# MQTTDoorBell.net
KiCad netlist of a schematic drawn in EAGLE
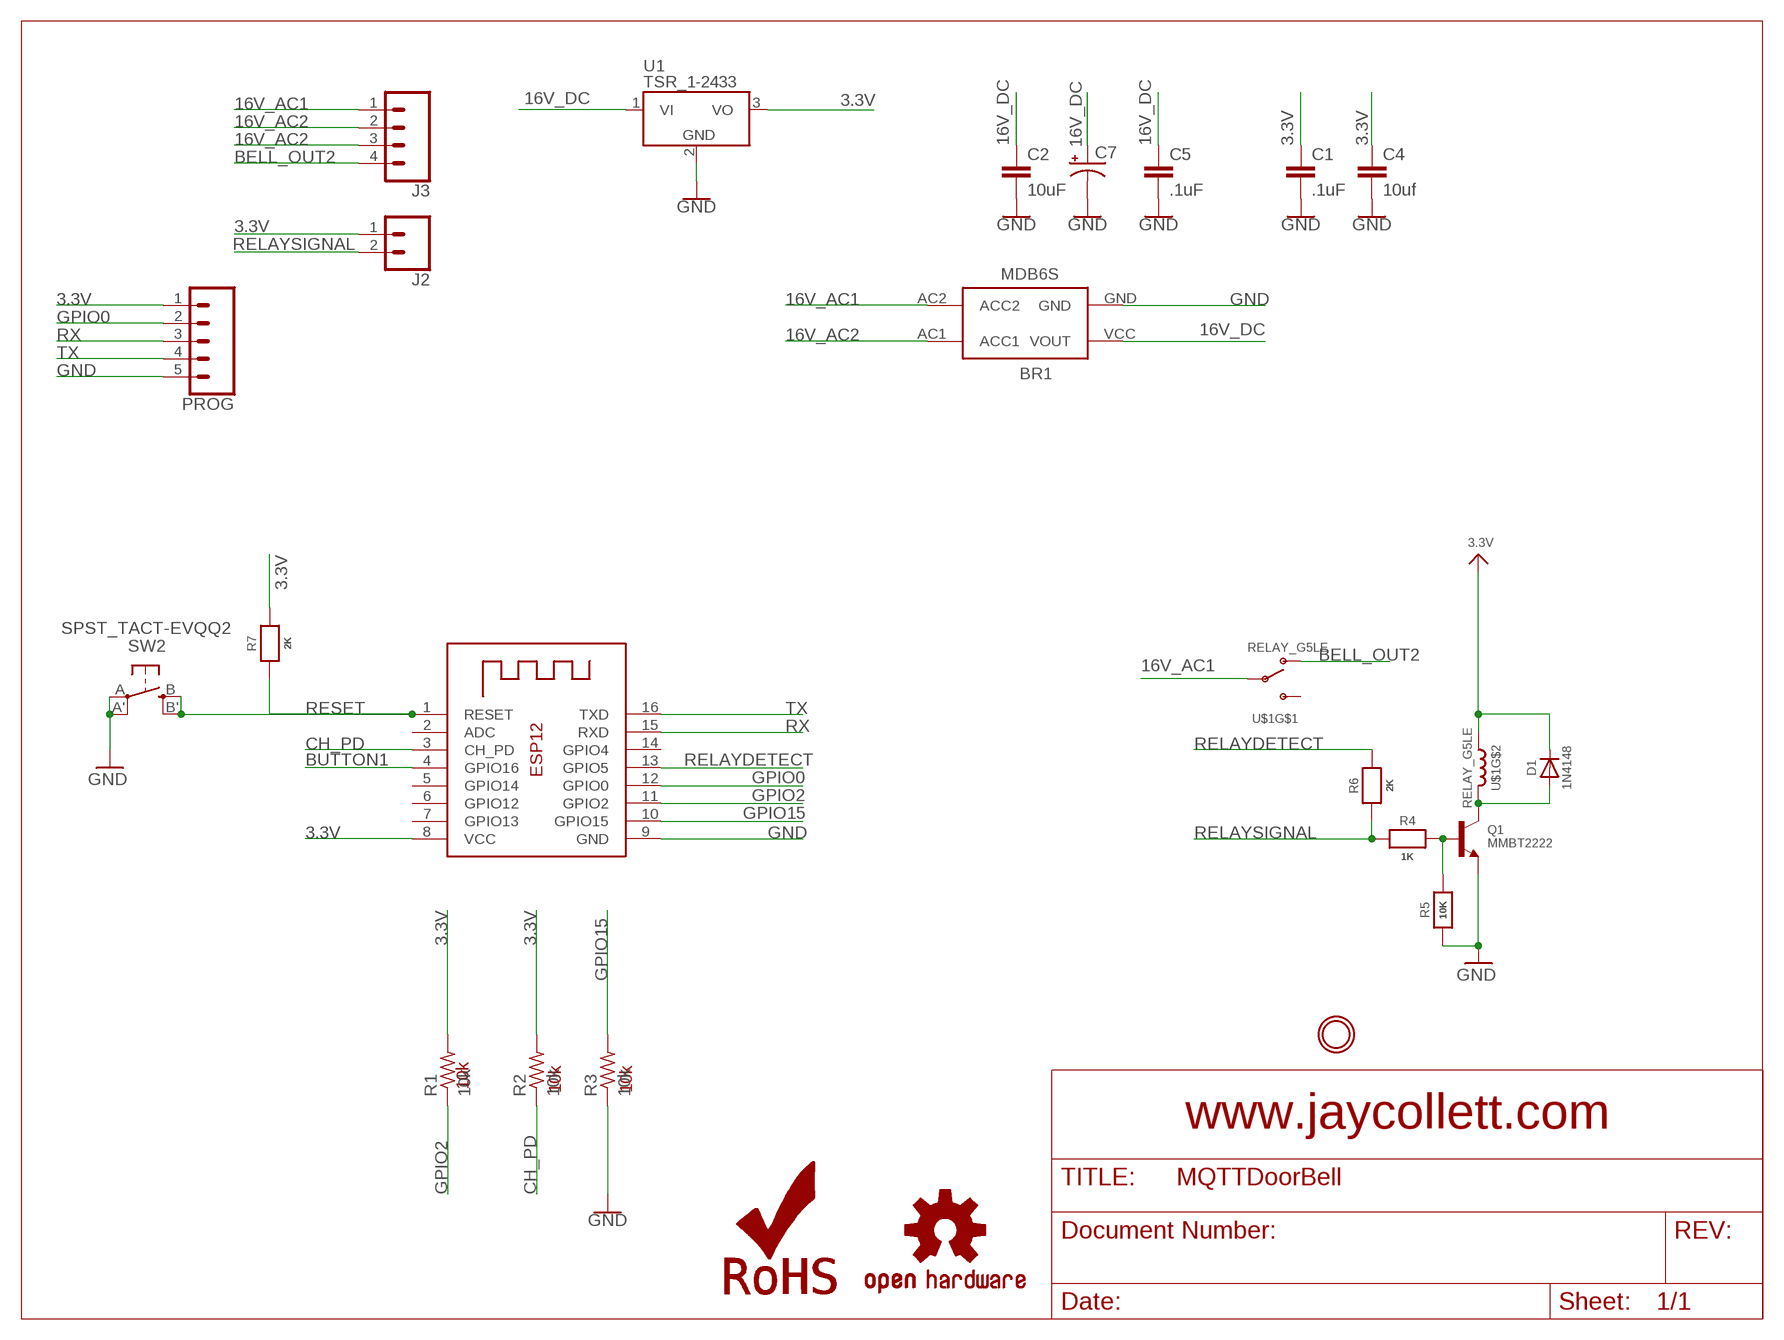
[diagram p0: schematic, sheet 1]

(export (version "E")
  (design (tool "Eeschema 10.0.6"))
  (components
    (comp (ref "BR1")
      (value "MDB6S")
      (footprint "eagle-import:MICRO-DIP")
      (libsource (lib "eagle-import") (part "MDB6S"))
    )
    (comp (ref "C1")
      (value ".1uF")
      (footprint "eagle-import:0805")
      (libsource (lib "eagle-import") (part "10UF-0805-10V-10%"))
    )
    (comp (ref "C2")
      (value "10uF")
      (footprint "eagle-import:0805")
      (libsource (lib "eagle-import") (part "10UF-0805-10V-10%"))
    )
    (comp (ref "C4")
      (value "10uf")
      (footprint "eagle-import:0805")
      (libsource (lib "eagle-import") (part "10UF-0805-10V-10%"))
    )
    (comp (ref "C5")
      (value ".1uF")
      (footprint "eagle-import:0805")
      (libsource (lib "eagle-import") (part "10UF-0805-10V-10%"))
    )
    (comp (ref "C7")
      (value "CPOL-USE5-10.5")
      (footprint "eagle-import:E5-10,5")
      (libsource (lib "eagle-import") (part "CPOL-USE5-10.5"))
    )
    (comp (ref "D1")
      (value "1N4148")
      (footprint "eagle-import:SOD-323")
      (libsource (lib "eagle-import") (part "DIODESOD-323"))
    )
    (comp (ref "J2")
      (value "CONN_023.5MM")
      (footprint "eagle-import:SCREWTERMINAL-3.5MM-2")
      (libsource (lib "eagle-import") (part "CONN_023.5MM"))
    )
    (comp (ref "J3")
      (value "CONN_04SCREW")
      (footprint "eagle-import:SCREWTERMINAL-3.5MM-4")
      (libsource (lib "eagle-import") (part "CONN_04SCREW"))
    )
    (comp (ref "LOGO1")
      (value "OSHW-LOGOMINI")
      (footprint "eagle-import:OSHW-LOGO-MINI")
      (libsource (lib "eagle-import") (part "OSHW-LOGOMINI"))
    )
    (comp (ref "LOGO2")
      (value "ROHS_LOGO")
      (footprint "eagle-import:ROHS_LOGO_0.18_IN")
      (libsource (lib "eagle-import") (part "ROHS_LOGO"))
    )
    (comp (ref "PROG")
      (value "CONN_05")
      (footprint "eagle-import:1X05")
      (libsource (lib "eagle-import") (part "CONN_05"))
    )
    (comp (ref "Q1")
      (value "MMBT2222")
      (footprint "eagle-import:SOT23-R")
      (libsource (lib "eagle-import") (part "TRANSISTOR_NPN"))
    )
    (comp (ref "R1")
      (value "10k")
      (footprint "eagle-import:M0805")
      (libsource (lib "eagle-import") (part "R-US_M0805"))
    )
    (comp (ref "R2")
      (value "10k")
      (footprint "eagle-import:M0805")
      (libsource (lib "eagle-import") (part "R-US_M0805"))
    )
    (comp (ref "R3")
      (value "10k")
      (footprint "eagle-import:M0805")
      (libsource (lib "eagle-import") (part "R-US_M0805"))
    )
    (comp (ref "R4")
      (value "1K")
      (footprint "eagle-import:0805-NO")
      (libsource (lib "eagle-import") (part "RESISTOR0805_NOOUTLINE"))
    )
    (comp (ref "R5")
      (value "10K")
      (footprint "eagle-import:0805-NO")
      (libsource (lib "eagle-import") (part "RESISTOR0805_NOOUTLINE"))
    )
    (comp (ref "R6")
      (value "2K")
      (footprint "eagle-import:0805-NO")
      (libsource (lib "eagle-import") (part "RESISTOR0805_NOOUTLINE"))
    )
    (comp (ref "R7")
      (value "2K")
      (footprint "eagle-import:0805-NO")
      (libsource (lib "eagle-import") (part "RESISTOR0805_NOOUTLINE"))
    )
    (comp (ref "SW2")
      (value "SPST_TACT-EVQQ2")
      (footprint "eagle-import:EVQ-Q2")
      (libsource (lib "eagle-import") (part "SPST_TACT-EVQQ2"))
    )
    (comp (ref "U$1")
      (value "RELAY_G5LE")
      (footprint "eagle-import:RELAY_G5LE-1")
      (fields (field (name "SPICEPREFIX") "B"))
      (libsource (lib "eagle-import") (part "RELAY_G5LE"))
    )
    (comp (ref "U$4")
      (value "MICROBUILDER_MOUNTINGHOLE3.0THIN")
      (footprint "eagle-import:MICROBUILDER_MOUNTINGHOLE_3.0_PLATEDTHIN")
      (libsource (lib "eagle-import") (part "MICROBUILDER_MOUNTINGHOLE3.0THIN"))
    )
    (comp (ref "U1")
      (value "TSR_1-2433")
      (footprint "eagle-import:TSR-1")
      (libsource (lib "eagle-import") (part "TSR_1-2433"))
    )
    (comp (ref "X1")
      (value "ESP-12")
      (footprint "eagle-import:ESP-12")
      (libsource (lib "eagle-import") (part "ESP-12"))
    )
  )
  (nets
    (net (code "1") (name "/16V_AC1") (class "Default")
      (node (ref "BR1") (pin "AC2") (pinfunction "ACC2_AC2") (pintype "input"))
      (node (ref "J3") (pin "1") (pinfunction "1_1") (pintype "passive"))
      (node (ref "U$1") (pin "1") (pinfunction "P_1") (pintype "passive"))
    )
    (net (code "2") (name "/16V_AC2") (class "Default")
      (node (ref "BR1") (pin "AC1") (pinfunction "ACC1_AC1") (pintype "input"))
      (node (ref "J3") (pin "2") (pinfunction "2_2") (pintype "passive"))
      (node (ref "J3") (pin "3") (pinfunction "3_3") (pintype "passive"))
    )
    (net (code "3") (name "/16V_DC") (class "Default")
      (node (ref "BR1") (pin "VCC") (pinfunction "VOUT_VCC") (pintype "bidirectional"))
      (node (ref "C2") (pin "1") (pinfunction "1_1") (pintype "passive"))
      (node (ref "C5") (pin "1") (pinfunction "1_1") (pintype "passive"))
      (node (ref "C7") (pin "+") (pinfunction "+_+") (pintype "passive"))
      (node (ref "U1") (pin "1") (pinfunction "VI_1") (pintype "power_in"))
    )
    (net (code "4") (name "/BELL_OUT2") (class "Default")
      (node (ref "J3") (pin "4") (pinfunction "4_4") (pintype "passive"))
      (node (ref "U$1") (pin "3") (pinfunction "O_3") (pintype "passive"))
    )
    (net (code "5") (name "/BUTTON1") (class "Default")
      (node (ref "X1") (pin "4") (pinfunction "GPIO16_4") (pintype "bidirectional"))
    )
    (net (code "6") (name "/CH_PD") (class "Default")
      (node (ref "R2") (pin "1") (pinfunction "1_1") (pintype "passive"))
      (node (ref "X1") (pin "3") (pinfunction "CH_PD_3") (pintype "input"))
    )
    (net (code "7") (name "/GPIO0") (class "Default")
      (node (ref "PROG") (pin "2") (pinfunction "2_2") (pintype "passive"))
      (node (ref "X1") (pin "12") (pinfunction "GPIO0_12") (pintype "bidirectional"))
    )
    (net (code "8") (name "/GPIO2") (class "Default")
      (node (ref "R1") (pin "1") (pinfunction "1_1") (pintype "passive"))
      (node (ref "X1") (pin "11") (pinfunction "GPIO2_11") (pintype "bidirectional"))
    )
    (net (code "9") (name "/GPIO15") (class "Default")
      (node (ref "R3") (pin "2") (pinfunction "2_2") (pintype "passive"))
      (node (ref "X1") (pin "10") (pinfunction "GPIO15_10") (pintype "bidirectional"))
    )
    (net (code "10") (name "/RELAYDETECT") (class "Default")
      (node (ref "R6") (pin "2") (pinfunction "2_2") (pintype "passive"))
      (node (ref "X1") (pin "13") (pinfunction "GPIO5_13") (pintype "bidirectional"))
    )
    (net (code "11") (name "/RELAYSIGNAL") (class "Default")
      (node (ref "J2") (pin "2") (pinfunction "2_2") (pintype "passive"))
      (node (ref "R4") (pin "1") (pinfunction "1_1") (pintype "passive"))
      (node (ref "R6") (pin "1") (pinfunction "1_1") (pintype "passive"))
    )
    (net (code "12") (name "/RESET") (class "Default")
      (node (ref "R7") (pin "1") (pinfunction "1_1") (pintype "passive"))
      (node (ref "SW2") (pin "B") (pinfunction "S_B") (pintype "passive"))
      (node (ref "SW2") (pin "B'") (pinfunction "S1_B'") (pintype "passive"))
      (node (ref "X1") (pin "1") (pinfunction "RESET_1") (pintype "input"))
    )
    (net (code "13") (name "/RX") (class "Default")
      (node (ref "PROG") (pin "3") (pinfunction "3_3") (pintype "passive"))
      (node (ref "X1") (pin "15") (pinfunction "RXD_15") (pintype "input"))
    )
    (net (code "14") (name "/TX") (class "Default")
      (node (ref "PROG") (pin "4") (pinfunction "4_4") (pintype "passive"))
      (node (ref "X1") (pin "16") (pinfunction "TXD_16") (pintype "output"))
    )
    (net (code "15") (name "3.3V") (class "Default")
      (node (ref "C1") (pin "1") (pinfunction "1_1") (pintype "passive"))
      (node (ref "C4") (pin "1") (pinfunction "1_1") (pintype "passive"))
      (node (ref "D1") (pin "C") (pinfunction "C_C") (pintype "passive"))
      (node (ref "J2") (pin "1") (pinfunction "1_1") (pintype "passive"))
      (node (ref "PROG") (pin "1") (pinfunction "1_1") (pintype "passive"))
      (node (ref "R1") (pin "2") (pinfunction "2_2") (pintype "passive"))
      (node (ref "R2") (pin "2") (pinfunction "2_2") (pintype "passive"))
      (node (ref "R7") (pin "2") (pinfunction "2_2") (pintype "passive"))
      (node (ref "U$1") (pin "2") (pinfunction "1_2") (pintype "passive"))
      (node (ref "U1") (pin "3") (pinfunction "VO_3") (pintype "power_in"))
      (node (ref "X1") (pin "8") (pinfunction "VCC_8") (pintype "power_in"))
    )
    (net (code "16") (name "GND") (class "Default")
      (node (ref "BR1") (pin "GND") (pinfunction "GND_GND") (pintype "bidirectional"))
      (node (ref "C1") (pin "2") (pinfunction "2_2") (pintype "passive"))
      (node (ref "C2") (pin "2") (pinfunction "2_2") (pintype "passive"))
      (node (ref "C4") (pin "2") (pinfunction "2_2") (pintype "passive"))
      (node (ref "C5") (pin "2") (pinfunction "2_2") (pintype "passive"))
      (node (ref "C7") (pin "-") (pinfunction "-_-") (pintype "passive"))
      (node (ref "PROG") (pin "5") (pinfunction "5_5") (pintype "passive"))
      (node (ref "Q1") (pin "2") (pinfunction "E_2") (pintype "passive"))
      (node (ref "R3") (pin "1") (pinfunction "1_1") (pintype "passive"))
      (node (ref "R5") (pin "1") (pinfunction "1_1") (pintype "passive"))
      (node (ref "SW2") (pin "A") (pinfunction "P_A") (pintype "passive"))
      (node (ref "SW2") (pin "A'") (pinfunction "P1_A'") (pintype "passive"))
      (node (ref "U1") (pin "2") (pinfunction "GND_2") (pintype "power_in"))
      (node (ref "X1") (pin "9") (pinfunction "GND_9") (pintype "power_in"))
    )
    (net (code "17") (name "Net-(Q1-B)") (class "Default")
      (node (ref "Q1") (pin "1") (pinfunction "B_1") (pintype "passive"))
      (node (ref "R4") (pin "2") (pinfunction "2_2") (pintype "passive"))
      (node (ref "R5") (pin "2") (pinfunction "2_2") (pintype "passive"))
    )
    (net (code "18") (name "Net-(Q1-C)") (class "Default")
      (node (ref "D1") (pin "A") (pinfunction "A_A") (pintype "passive"))
      (node (ref "Q1") (pin "3") (pinfunction "C_3") (pintype "passive"))
      (node (ref "U$1") (pin "5") (pinfunction "2_5") (pintype "passive"))
    )
    (net (code "19") (name "unconnected-(U$1A-S-Pad4)") (class "Default")
      (node (ref "U$1") (pin "4") (pinfunction "S_4") (pintype "passive"))
    )
    (net (code "20") (name "unconnected-(X1-ADC-Pad2)") (class "Default")
      (node (ref "X1") (pin "2") (pinfunction "ADC_2") (pintype "passive"))
    )
    (net (code "21") (name "unconnected-(X1-GPIO4-Pad14)") (class "Default")
      (node (ref "X1") (pin "14") (pinfunction "GPIO4_14") (pintype "bidirectional"))
    )
    (net (code "22") (name "unconnected-(X1-GPIO12-Pad6)") (class "Default")
      (node (ref "X1") (pin "6") (pinfunction "GPIO12_6") (pintype "bidirectional"))
    )
    (net (code "23") (name "unconnected-(X1-GPIO13-Pad7)") (class "Default")
      (node (ref "X1") (pin "7") (pinfunction "GPIO13_7") (pintype "bidirectional"))
    )
    (net (code "24") (name "unconnected-(X1-GPIO14-Pad5)") (class "Default")
      (node (ref "X1") (pin "5") (pinfunction "GPIO14_5") (pintype "bidirectional"))
    )
  )
)
